# FOTA_MicroController_Power_Switch.net
KiCad netlist of a schematic drawn in Altium Designer
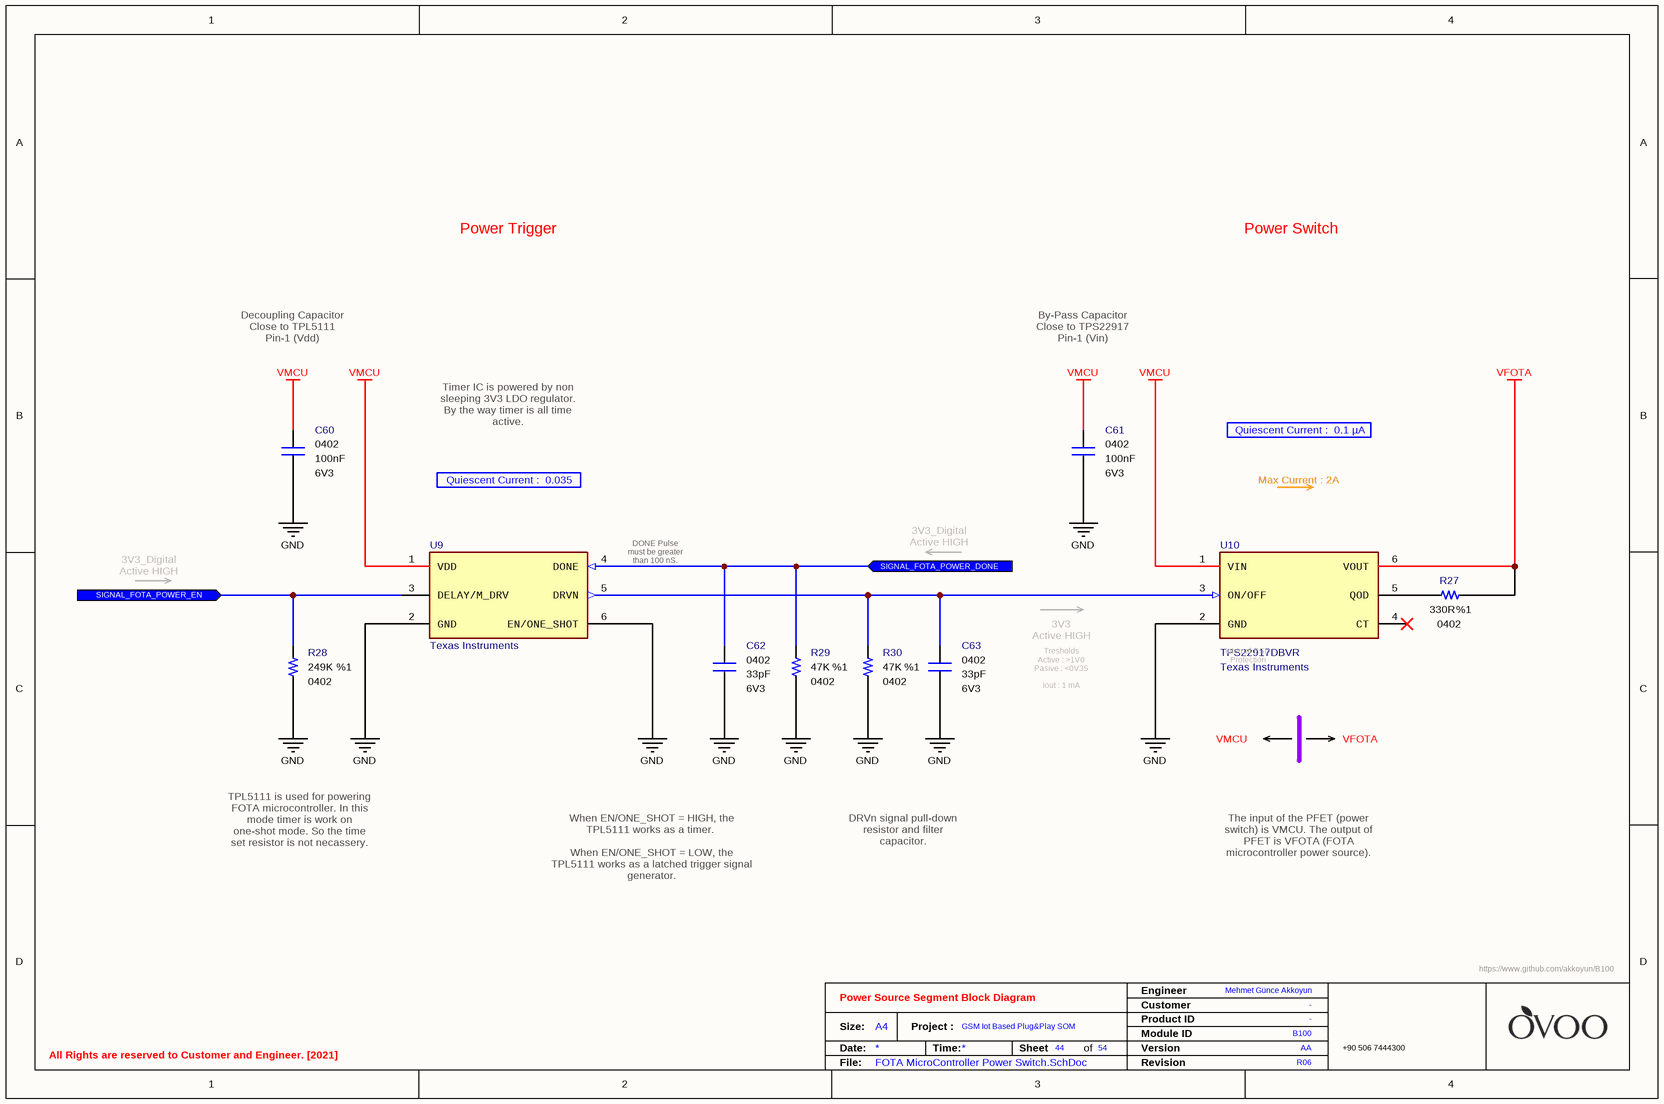
[diagram p0: FOTA MicroController Power Switch.SchDoc]

(export (version "E")
  (design (tool "Eeschema 10.0.6"))
  (components
    (comp (ref "C60")
      (value "100nF")
      (footprint "CAPACITOR_0402")
      (description "Capacitor - 100nF [0402-6V3] (Ceramic)")
      (fields
        (field (name "TOLERANCE") "%10")
        (field (name "CASE") "0402")
        (field (name "VOLTAGE") "6V3")
        (field (name "MANUFACTURER PART NUMBER") "04026D104KAT4A")
      )
      (libsource (lib "Ovoo_Library") (part "Capacitor - 100nF [0402-6V3]"))
    )
    (comp (ref "C61")
      (value "100nF")
      (footprint "CAPACITOR_0402")
      (description "Capacitor - 100nF [0402-6V3] (Ceramic)")
      (fields
        (field (name "CASE") "0402")
        (field (name "TOLERANCE") "%10")
        (field (name "VOLTAGE") "6V3")
        (field (name "MANUFACTURER PART NUMBER") "04026D104KAT4A")
      )
      (libsource (lib "Ovoo_Library") (part "Capacitor - 100nF [0402-6V3]"))
    )
    (comp (ref "C62")
      (value "33pF")
      (footprint "CAPACITOR_0402")
      (description "Capacitor - 33pF [0402] (Ceramic)")
      (fields
        (field (name "TOLERANCE") "10%")
        (field (name "CASE") "0402")
        (field (name "VOLTAGE") "6V3")
        (field (name "MANUFACTURER PART NUMBER") "C0402C330J9RACAUTO")
      )
      (libsource (lib "Ovoo_Library") (part "Capacitor - 33pF [0402-6V3]"))
    )
    (comp (ref "C63")
      (value "33pF")
      (footprint "CAPACITOR_0402")
      (description "Capacitor - 33pF [0402] (Ceramic)")
      (fields
        (field (name "TOLERANCE") "10%")
        (field (name "CASE") "0402")
        (field (name "VOLTAGE") "6V3")
        (field (name "MANUFACTURER PART NUMBER") "C0402C330J9RACAUTO")
      )
      (libsource (lib "Ovoo_Library") (part "Capacitor - 33pF [0402-6V3]"))
    )
    (comp (ref "R27")
      (value "330R")
      (footprint "RESISTOR_0402")
      (description "Thick Film Resistors - SMD 1/16 W 330 Ohm 1%")
      (fields
        (field (name "TOLERANCE") "%1")
        (field (name "CASE") "0402")
        (field (name "MANUFACTURER PART NUMBER") "CRCW0402330RFKED")
        (field (name "MOUSER PART NUMBER") "71-CRCW0402-330-E3")
      )
      (libsource (lib "Ovoo_Library") (part "Resistor - 330R"))
    )
    (comp (ref "R28")
      (value "249K")
      (footprint "RESISTOR_0402")
      (description "Thick Film Resistors - SMD 1/16 W 249 Kohms 1%")
      (fields
        (field (name "TOLERANCE") "%1")
        (field (name "CASE") "0402")
        (field (name "MANUFACTURER PART NUMBER") "CRCW0402249KFKED")
        (field (name "MOUSER PART NUMBER") "71-CRCW0402-249K-E3")
      )
      (libsource (lib "Ovoo_Library") (part "Resistor - 249K"))
    )
    (comp (ref "R29")
      (value "47K")
      (footprint "RESISTOR_0402")
      (description "Thick Film Resistors - SMD 1/16 W 47 Kohms 1%")
      (fields
        (field (name "TOLERANCE") "%1")
        (field (name "CASE") "0402")
        (field (name "MANUFACTURER PART NUMBER") "CRCW040247K0FKED")
        (field (name "MOUSER PART NUMBER") "71-CRCW0402-47K-E3")
      )
      (libsource (lib "Ovoo_Library") (part "Resistor - 47K"))
    )
    (comp (ref "R30")
      (value "47K")
      (footprint "RESISTOR_0402")
      (description "Thick Film Resistors - SMD 1/16 W 47 Kohms 1%")
      (fields
        (field (name "TOLERANCE") "%1")
        (field (name "CASE") "0402")
        (field (name "MANUFACTURER PART NUMBER") "CRCW040247K0FKED")
        (field (name "MOUSER PART NUMBER") "71-CRCW0402-47K-E3")
      )
      (libsource (lib "Ovoo_Library") (part "Resistor - 47K"))
    )
    (comp (ref "U9")
      (value "Nanopower Timer IC")
      (footprint "SOT-23-6")
      (fields
        (field (name "MOUSER PART NUMBER") "595-TPL5111DDCT")
        (field (name "MANUFACTURER PART NUMBER") "TPL5111DDCT")
        (field (name "MANUFACTURER NAME") "Texas Instruments")
      )
      (libsource (lib "Ovoo_Library") (part "IC - TPL5111"))
    )
    (comp (ref "U10")
      (value "Power Switch")
      (footprint "SOT-23-6")
      (description "Power Switch MosFet")
      (fields
        (field (name "MOUSER PART NUMBER") "595-TPS22917DBVR")
        (field (name "MANUFACTURER PART NUMBER") "TPS22917DBVR")
        (field (name "MANUFACTURER NAME") "Texas Instruments")
      )
      (libsource (lib "Ovoo_Library") (part "IC - TPS22917DBVR"))
    )
  )
  (nets
    (net (code "1") (name "/SIGNAL_FOTA_POWER_DONE") (class "Default")
      (node (ref "C62") (pin "2") (pinfunction "2_2") (pintype "passive"))
      (node (ref "R29") (pin "2") (pinfunction "2_2") (pintype "passive"))
      (node (ref "U9") (pin "4") (pinfunction "DONE_4") (pintype "input"))
    )
    (net (code "2") (name "/SIGNAL_FOTA_POWER_EN") (class "Default")
      (node (ref "R28") (pin "2") (pinfunction "2_2") (pintype "passive"))
      (node (ref "U9") (pin "3") (pinfunction "DELAY/M_DRV_3") (pintype "passive"))
    )
    (net (code "3") (name "GND") (class "Default")
      (node (ref "C60") (pin "1") (pinfunction "1_1") (pintype "passive"))
      (node (ref "C61") (pin "2") (pinfunction "2_2") (pintype "passive"))
      (node (ref "C62") (pin "1") (pinfunction "1_1") (pintype "passive"))
      (node (ref "C63") (pin "1") (pinfunction "1_1") (pintype "passive"))
      (node (ref "R28") (pin "1") (pinfunction "1_1") (pintype "passive"))
      (node (ref "R29") (pin "1") (pinfunction "1_1") (pintype "passive"))
      (node (ref "R30") (pin "1") (pinfunction "1_1") (pintype "passive"))
      (node (ref "U10") (pin "2") (pinfunction "GND_2") (pintype "power_in"))
      (node (ref "U9") (pin "2") (pinfunction "GND_2") (pintype "power_in"))
      (node (ref "U9") (pin "6") (pinfunction "EN/ONE_SHOT_6") (pintype "passive"))
    )
    (net (code "4") (name "Net-(U10-ON{slash}OFF)") (class "Default")
      (node (ref "C63") (pin "2") (pinfunction "2_2") (pintype "passive"))
      (node (ref "R30") (pin "2") (pinfunction "2_2") (pintype "passive"))
      (node (ref "U10") (pin "3") (pinfunction "ON/OFF_3") (pintype "input"))
      (node (ref "U9") (pin "5") (pinfunction "DRVN_5") (pintype "output"))
    )
    (net (code "5") (name "Net-(U10-QOD)") (class "Default")
      (node (ref "R27") (pin "2") (pinfunction "2_2") (pintype "passive"))
      (node (ref "U10") (pin "5") (pinfunction "QOD_5") (pintype "power_in"))
    )
    (net (code "6") (name "VFOTA") (class "Default")
      (node (ref "R27") (pin "1") (pinfunction "1_1") (pintype "passive"))
      (node (ref "U10") (pin "6") (pinfunction "VOUT_6") (pintype "power_in"))
    )
    (net (code "7") (name "VMCU") (class "Default")
      (node (ref "C60") (pin "2") (pinfunction "2_2") (pintype "passive"))
      (node (ref "C61") (pin "1") (pinfunction "1_1") (pintype "passive"))
      (node (ref "U10") (pin "1") (pinfunction "VIN_1") (pintype "power_in"))
      (node (ref "U9") (pin "1") (pinfunction "VDD_1") (pintype "power_in"))
    )
    (net (code "8") (name "unconnected-(U10-CT-Pad4)") (class "Default")
      (node (ref "U10") (pin "4") (pinfunction "CT_4") (pintype "power_in+no_connect"))
    )
  )
)
